# Arak-DAC.net
KiCad netlist of a schematic drawn in Altium Designer
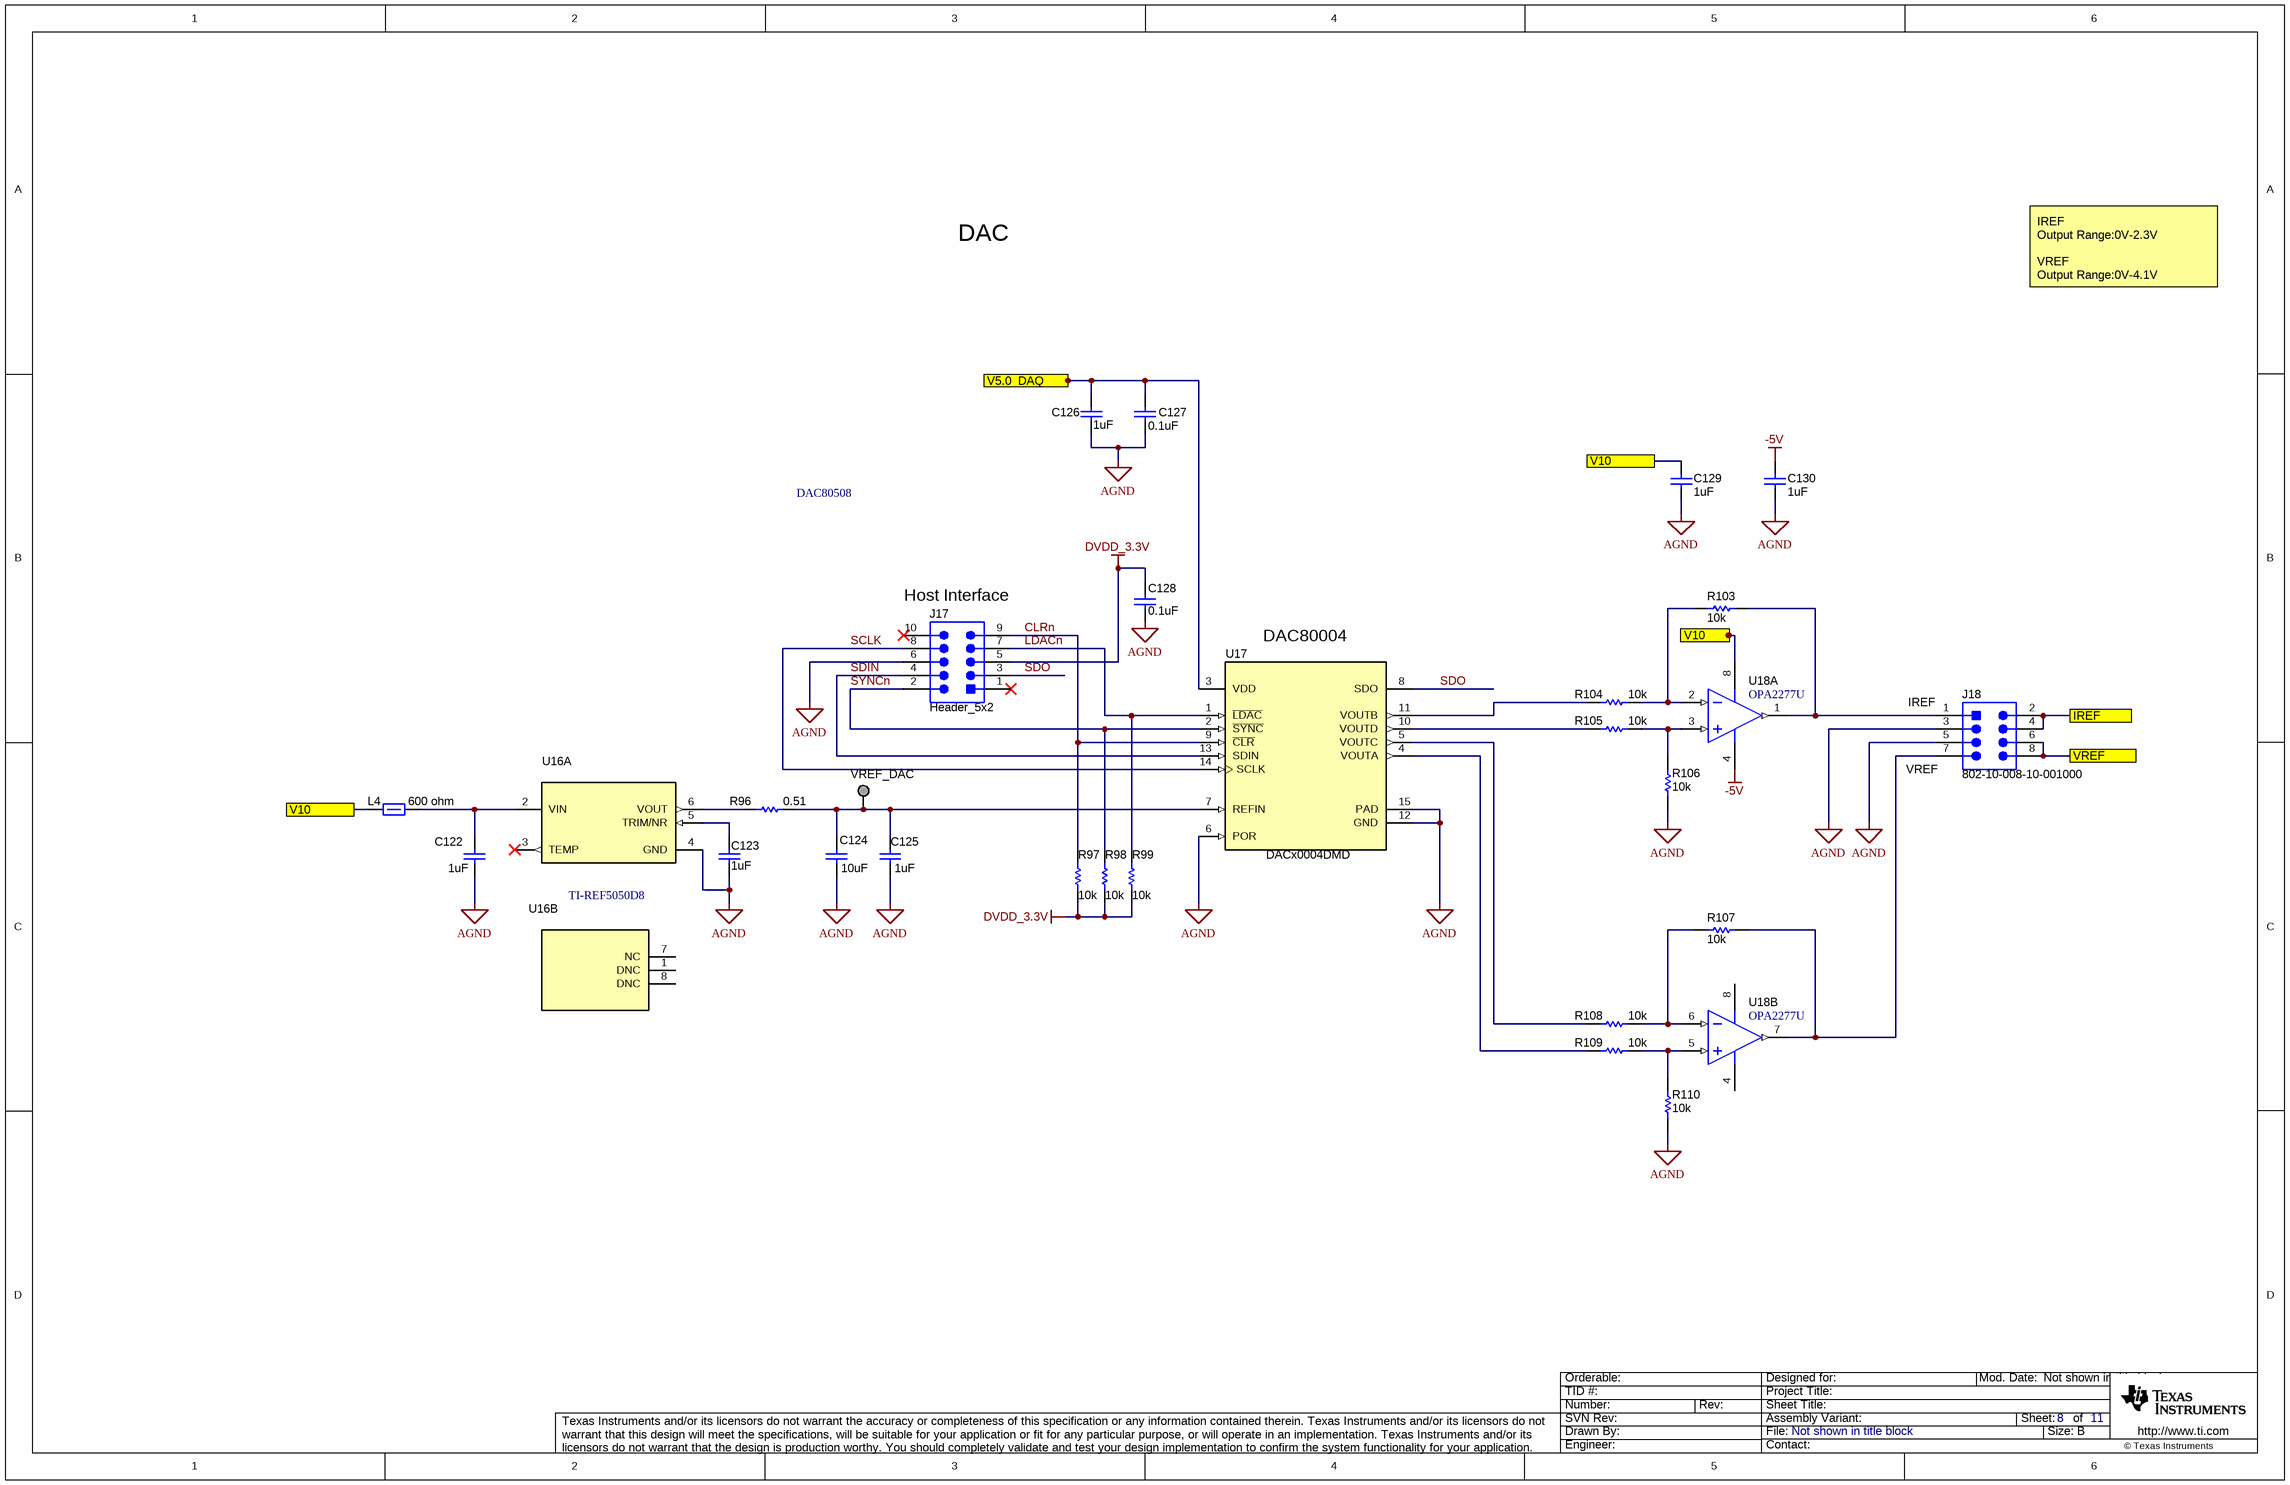
[diagram p0: Arak-DAC.SchDoc]

(export (version "E")
  (design (tool "Eeschema 10.0.6"))
  (components
    (comp (ref "C122")
      (value "Capacitor")
      (footprint "1206")
      (description "CAP, CERM, 1 uF, 25 V, +/- 10%, X7R, 1206")
      (fields
        (field (name "PARTNUMBER") "12063C105KAT2A")
        (field (name "VALUEDISPLAYED") "1uF")
        (field (name "MANUFACTURER") "AVX")
        (field (name "PUBLISHER") "Texas Instruments")
      )
      (libsource (lib "Altium Vault - TI") (part "CMP-0008509-2"))
    )
    (comp (ref "C123")
      (value "Capacitor")
      (footprint "1206")
      (description "CAP, CERM, 1 uF, 25 V, +/- 10%, X7R, 1206")
      (fields
        (field (name "PARTNUMBER") "12063C105KAT2A")
        (field (name "VALUEDISPLAYED") "1uF")
        (field (name "MANUFACTURER") "AVX")
        (field (name "PUBLISHER") "Texas Instruments")
      )
      (libsource (lib "Altium Vault - TI") (part "CMP-0008509-2"))
    )
    (comp (ref "C124")
      (value "Capacitor")
      (footprint "0805_HV")
      (description "CAP, CERM, 10 uF, 35 V, +/- 10%, X6S, 0805")
      (fields
        (field (name "PARTNUMBER") "GRM21BC8YA106KE11L")
        (field (name "VALUEDISPLAYED") "10uF")
        (field (name "MANUFACTURER") "MuRata")
        (field (name "PUBLISHER") "Texas Instruments")
      )
      (libsource (lib "Altium Vault - TI") (part "CMP-0008273-1"))
    )
    (comp (ref "C125")
      (value "Capacitor")
      (footprint "1206")
      (description "CAP, CERM, 1 uF, 25 V, +/- 10%, X7R, 1206")
      (fields
        (field (name "PARTNUMBER") "12063C105KAT2A")
        (field (name "VALUEDISPLAYED") "1uF")
        (field (name "MANUFACTURER") "AVX")
        (field (name "PUBLISHER") "Texas Instruments")
      )
      (libsource (lib "Altium Vault - TI") (part "CMP-0008509-2"))
    )
    (comp (ref "C126")
      (value "Capacitor")
      (footprint "1206")
      (description "CAP, CERM, 1 uF, 25 V, +/- 10%, X7R, 1206")
      (fields
        (field (name "PARTNUMBER") "12063C105KAT2A")
        (field (name "VALUEDISPLAYED") "1uF")
        (field (name "MANUFACTURER") "AVX")
        (field (name "PUBLISHER") "Texas Instruments")
      )
      (libsource (lib "Altium Vault - TI") (part "CMP-0008509-2"))
    )
    (comp (ref "C127")
      (value "Capacitor")
      (footprint "0603")
      (description "CAP, CERM, 0.1 uF, 16 V, +/- 5%, X7R, 0603")
      (fields
        (field (name "PARTNUMBER") "C0603C104J4RACTU")
        (field (name "VALUEDISPLAYED") "0.1uF")
        (field (name "MANUFACTURER") "Kemet")
        (field (name "PUBLISHER") "Texas Instruments")
      )
      (libsource (lib "Altium Vault - TI") (part "CMP-0006857-4"))
    )
    (comp (ref "C128")
      (value "Capacitor")
      (footprint "0603")
      (description "CAP, CERM, 0.1 uF, 16 V, +/- 5%, X7R, 0603")
      (fields
        (field (name "PARTNUMBER") "C0603C104J4RACTU")
        (field (name "VALUEDISPLAYED") "0.1uF")
        (field (name "MANUFACTURER") "Kemet")
        (field (name "PUBLISHER") "Texas Instruments")
      )
      (libsource (lib "Altium Vault - TI") (part "CMP-0006857-4"))
    )
    (comp (ref "C129")
      (value "Capacitor")
      (footprint "0603")
      (description "CAP, CERM, 1 uF, 35 V, +/- 10%, X7R, AEC-Q200 Grade 1, 0603")
      (fields
        (field (name "PARTNUMBER") "CGA3E1X7R1V105K080AC")
        (field (name "VALUEDISPLAYED") "1uF")
        (field (name "MANUFACTURER") "TDK")
        (field (name "PUBLISHER") "Texas Instruments")
      )
      (libsource (lib "Altium Vault - TI") (part "CMP-0007067-4"))
    )
    (comp (ref "C130")
      (value "Capacitor")
      (footprint "0603")
      (description "CAP, CERM, 1 uF, 35 V, +/- 10%, X7R, AEC-Q200 Grade 1, 0603")
      (fields
        (field (name "PARTNUMBER") "CGA3E1X7R1V105K080AC")
        (field (name "VALUEDISPLAYED") "1uF")
        (field (name "MANUFACTURER") "TDK")
        (field (name "PUBLISHER") "Texas Instruments")
      )
      (libsource (lib "Altium Vault - TI") (part "CMP-0007067-4"))
    )
    (comp (ref "J17")
      (value "Header_5x2")
      (footprint "Assman_AWHW-10G-0x02-T")
      (description "Header(Shrouded), 2.54mm, 5x2, Gold, TH")
      (fields
        (field (name "PARTNUMBER") "AWHW-10G-0202-T")
        (field (name "MANUFACTURER") "Assman WSW")
        (field (name "PUBLISHER") "Texas Instruments")
      )
      (libsource (lib "Altium Vault - TI") (part "CMP-0075161-1"))
    )
    (comp (ref "J18")
      (value "802-10-008-10-001000")
      (footprint "Mill-Max_802-10-008-10-001000")
      (description "Header, 2.54 mm, 4x2, Gold, TH")
      (fields (field (name "MANUFACTURER") "Mill-Max") (field (name "PUBLISHER") "Texas Instruments"))
      (libsource (lib "Altium Vault - TI") (part "CMP-0055096-1"))
    )
    (comp (ref "L4")
      (value "600 ohm")
      (footprint "0603")
      (description "Ferrite Bead, 600 ohm @ 100 MHz, 1 A, 0603")
      (fields
        (field (name "PARTNUMBER") "742792651")
        (field (name "MANUFACTURER") "Wurth Elektronik")
        (field (name "PUBLISHER") "Texas Instruments")
      )
      (libsource (lib "Altium Vault - TI") (part "Ferrite_Bead"))
    )
    (comp (ref "R96")
      (value "Resistor")
      (footprint "0603")
      (description "RES, 0.51, 1%, 0.1 W, AEC-Q200 Grade 1, 0603")
      (fields
        (field (name "PARTNUMBER") "ERJ-3RQFR51V")
        (field (name "VALUEDISPLAYED") "0.51")
        (field (name "MANUFACTURER") "Panasonic")
        (field (name "PUBLISHER") "Texas Instruments")
      )
      (libsource (lib "Altium Vault - TI") (part "CMP-0022717-2"))
    )
    (comp (ref "R97")
      (value "Resistor")
      (footprint "0603")
      (description "RES, 10 k, 5%, 0.1 W, AEC-Q200 Grade 0, 0603")
      (fields
        (field (name "PARTNUMBER") "CRCW060310K0JNEA")
        (field (name "VALUEDISPLAYED") "10k")
        (field (name "MANUFACTURER") "Vishay-Dale")
      )
      (libsource (lib "Altium Vault - TI") (part "CMP-0025701-4"))
    )
    (comp (ref "R98")
      (value "Resistor")
      (footprint "0603")
      (description "RES, 10 k, 5%, 0.1 W, AEC-Q200 Grade 0, 0603")
      (fields
        (field (name "PARTNUMBER") "CRCW060310K0JNEA")
        (field (name "VALUEDISPLAYED") "10k")
        (field (name "MANUFACTURER") "Vishay-Dale")
      )
      (libsource (lib "Altium Vault - TI") (part "CMP-0025701-4"))
    )
    (comp (ref "R99")
      (value "Resistor")
      (footprint "0603")
      (description "RES, 10 k, 5%, 0.1 W, AEC-Q200 Grade 0, 0603")
      (fields
        (field (name "PARTNUMBER") "CRCW060310K0JNEA")
        (field (name "VALUEDISPLAYED") "10k")
        (field (name "MANUFACTURER") "Vishay-Dale")
      )
      (libsource (lib "Altium Vault - TI") (part "CMP-0025701-4"))
    )
    (comp (ref "R103")
      (value "Resistor")
      (footprint "0603")
      (description "RES, 10 k, 5%, 0.1 W, AEC-Q200 Grade 0, 0603")
      (fields
        (field (name "PARTNUMBER") "CRCW060310K0JNEA")
        (field (name "VALUEDISPLAYED") "10k")
        (field (name "MANUFACTURER") "Vishay-Dale")
      )
      (libsource (lib "Altium Vault - TI") (part "CMP-0025701-4"))
    )
    (comp (ref "R104")
      (value "Resistor")
      (footprint "0603")
      (description "RES, 10 k, 5%, 0.1 W, AEC-Q200 Grade 0, 0603")
      (fields
        (field (name "PARTNUMBER") "CRCW060310K0JNEA")
        (field (name "VALUEDISPLAYED") "10k")
        (field (name "MANUFACTURER") "Vishay-Dale")
      )
      (libsource (lib "Altium Vault - TI") (part "CMP-0025701-4"))
    )
    (comp (ref "R105")
      (value "Resistor")
      (footprint "0603")
      (description "RES, 10 k, 5%, 0.1 W, AEC-Q200 Grade 0, 0603")
      (fields
        (field (name "PARTNUMBER") "CRCW060310K0JNEA")
        (field (name "VALUEDISPLAYED") "10k")
        (field (name "MANUFACTURER") "Vishay-Dale")
      )
      (libsource (lib "Altium Vault - TI") (part "CMP-0025701-4"))
    )
    (comp (ref "R106")
      (value "Resistor")
      (footprint "0603")
      (description "RES, 10 k, 5%, 0.1 W, AEC-Q200 Grade 0, 0603")
      (fields
        (field (name "PARTNUMBER") "CRCW060310K0JNEA")
        (field (name "VALUEDISPLAYED") "10k")
        (field (name "MANUFACTURER") "Vishay-Dale")
      )
      (libsource (lib "Altium Vault - TI") (part "CMP-0025701-4"))
    )
    (comp (ref "R107")
      (value "Resistor")
      (footprint "0603")
      (description "RES, 10 k, 5%, 0.1 W, AEC-Q200 Grade 0, 0603")
      (fields
        (field (name "PARTNUMBER") "CRCW060310K0JNEA")
        (field (name "VALUEDISPLAYED") "10k")
        (field (name "MANUFACTURER") "Vishay-Dale")
      )
      (libsource (lib "Altium Vault - TI") (part "CMP-0025701-4"))
    )
    (comp (ref "R108")
      (value "Resistor")
      (footprint "0603")
      (description "RES, 10 k, 5%, 0.1 W, AEC-Q200 Grade 0, 0603")
      (fields
        (field (name "PARTNUMBER") "CRCW060310K0JNEA")
        (field (name "VALUEDISPLAYED") "10k")
        (field (name "MANUFACTURER") "Vishay-Dale")
      )
      (libsource (lib "Altium Vault - TI") (part "CMP-0025701-4"))
    )
    (comp (ref "R109")
      (value "Resistor")
      (footprint "0603")
      (description "RES, 10 k, 5%, 0.1 W, AEC-Q200 Grade 0, 0603")
      (fields
        (field (name "PARTNUMBER") "CRCW060310K0JNEA")
        (field (name "VALUEDISPLAYED") "10k")
        (field (name "MANUFACTURER") "Vishay-Dale")
      )
      (libsource (lib "Altium Vault - TI") (part "CMP-0025701-4"))
    )
    (comp (ref "R110")
      (value "Resistor")
      (footprint "0603")
      (description "RES, 10 k, 5%, 0.1 W, AEC-Q200 Grade 0, 0603")
      (fields
        (field (name "PARTNUMBER") "CRCW060310K0JNEA")
        (field (name "VALUEDISPLAYED") "10k")
        (field (name "MANUFACTURER") "Vishay-Dale")
      )
      (libsource (lib "Altium Vault - TI") (part "CMP-0025701-4"))
    )
    (comp (ref "U16")
      (value "TI-REF5050D8")
      (footprint "D0008A_N")
      (fields (field (name "PARTNUMBER") "REF5050AID") (field (name "MANUFACTURER") "Texas Instruments"))
      (libsource (lib "Altium Vault - TI") (part "CMP-0032617-1"))
    )
    (comp (ref "U17")
      (value "DACx0004DMD")
      (footprint "DMD0014A")
      (description "QUAD 16-BIT, 1LSB INL, BUFFERED, VOLTAGE-OUTPUT DIGITAL-to-ANALOG CONVERTERS, DMD0014A (VSON-14)")
      (fields
        (field (name "PARTNUMBER") "DAC80004IDMD")
        (field (name "MANUFACTURER") "Texas Instruments")
        (field (name "PUBLISHER") "Texas Instruments")
      )
      (libsource (lib "Altium Vault - TI") (part "DACx0004DMD"))
    )
    (comp (ref "U18")
      (value "OPA2277U")
      (footprint "D0008A_N")
      (fields (field (name "MANUFACTURER") "Texas Instruments"))
      (libsource (lib "Altium Vault - TI") (part "CMP-0040655-1"))
    )
    (comp (ref "VREF_DAC")
      (value "Pogo Pad")
      (footprint "PogoPad")
      (description "Pad for Pogo Pin Connector")
      (fields (field (name "SYMBOLCREATOR") "codlsc") (field (name "PUBLISHER") "Texas Instruments"))
      (libsource (lib "MiscParts") (part "PogoPad"))
    )
  )
  (nets
    (net (code "1") (name "-5V") (class "Default")
      (node (ref "C130") (pin "1") (pinfunction "1_1") (pintype "passive"))
      (node (ref "U18") (pin "4") (pinfunction "V-_4") (pintype "power_in"))
    )
    (net (code "2") (name "/CLRn") (class "Default")
      (node (ref "J17") (pin "9") (pinfunction "9_9") (pintype "passive"))
      (node (ref "R97") (pin "2") (pinfunction "2_2") (pintype "passive"))
      (node (ref "U17") (pin "9") (pinfunction "CLR_9") (pintype "input"))
    )
    (net (code "3") (name "/IREF") (class "Default")
      (node (ref "J18") (pin "2") (pinfunction "2_2") (pintype "passive"))
      (node (ref "J18") (pin "4") (pinfunction "4_4") (pintype "passive"))
    )
    (net (code "4") (name "/LDACn") (class "Default")
      (node (ref "J17") (pin "7") (pinfunction "7_7") (pintype "passive"))
      (node (ref "R99") (pin "2") (pinfunction "2_2") (pintype "passive"))
      (node (ref "U17") (pin "1") (pinfunction "LDAC_1") (pintype "input"))
    )
    (net (code "5") (name "/SCLK") (class "Default")
      (node (ref "J17") (pin "8") (pinfunction "8_8") (pintype "passive"))
      (node (ref "U17") (pin "14") (pinfunction "SCLK_14") (pintype "input"))
    )
    (net (code "6") (name "/SDIN") (class "Default")
      (node (ref "J17") (pin "4") (pinfunction "4_4") (pintype "passive"))
      (node (ref "U17") (pin "13") (pinfunction "SDIN_13") (pintype "input"))
    )
    (net (code "7") (name "/SDO") (class "Default")
      (node (ref "J17") (pin "3") (pinfunction "3_3") (pintype "passive"))
      (node (ref "U17") (pin "8") (pinfunction "SDO_8") (pintype "tri_state"))
    )
    (net (code "8") (name "/SYNCn") (class "Default")
      (node (ref "J17") (pin "2") (pinfunction "2_2") (pintype "passive"))
      (node (ref "R98") (pin "2") (pinfunction "2_2") (pintype "passive"))
      (node (ref "U17") (pin "2") (pinfunction "SYNC_2") (pintype "input"))
    )
    (net (code "9") (name "/V5.0_DAQ") (class "Default")
      (node (ref "C126") (pin "1") (pinfunction "1_1") (pintype "passive"))
      (node (ref "C127") (pin "1") (pinfunction "1_1") (pintype "passive"))
      (node (ref "U17") (pin "3") (pinfunction "VDD_3") (pintype "power_in"))
    )
    (net (code "10") (name "/V10") (class "Default")
      (node (ref "C129") (pin "1") (pinfunction "1_1") (pintype "passive"))
      (node (ref "L4") (pin "1") (pinfunction "1_1") (pintype "passive"))
      (node (ref "U18") (pin "8") (pinfunction "V+_8") (pintype "power_in"))
    )
    (net (code "11") (name "/VREF") (class "Default")
      (node (ref "J18") (pin "6") (pinfunction "6_6") (pintype "passive"))
      (node (ref "J18") (pin "8") (pinfunction "8_8") (pintype "passive"))
    )
    (net (code "12") (name "AGND") (class "Default")
      (node (ref "C122") (pin "2") (pinfunction "2_2") (pintype "passive"))
      (node (ref "C123") (pin "2") (pinfunction "2_2") (pintype "passive"))
      (node (ref "C124") (pin "2") (pinfunction "2_2") (pintype "passive"))
      (node (ref "C125") (pin "2") (pinfunction "2_2") (pintype "passive"))
      (node (ref "C126") (pin "2") (pinfunction "2_2") (pintype "passive"))
      (node (ref "C127") (pin "2") (pinfunction "2_2") (pintype "passive"))
      (node (ref "C128") (pin "2") (pinfunction "2_2") (pintype "passive"))
      (node (ref "C129") (pin "2") (pinfunction "2_2") (pintype "passive"))
      (node (ref "C130") (pin "2") (pinfunction "2_2") (pintype "passive"))
      (node (ref "J17") (pin "6") (pinfunction "6_6") (pintype "passive"))
      (node (ref "J18") (pin "3") (pinfunction "3_3") (pintype "passive"))
      (node (ref "J18") (pin "5") (pinfunction "5_5") (pintype "passive"))
      (node (ref "R106") (pin "1") (pinfunction "1_1") (pintype "passive"))
      (node (ref "R110") (pin "1") (pinfunction "1_1") (pintype "passive"))
      (node (ref "U16") (pin "4") (pinfunction "GND_4") (pintype "power_in"))
      (node (ref "U17") (pin "12") (pinfunction "GND_12") (pintype "power_in"))
      (node (ref "U17") (pin "15") (pinfunction "PAD_15") (pintype "passive"))
      (node (ref "U17") (pin "6") (pinfunction "POR_6") (pintype "input"))
    )
    (net (code "13") (name "DVDD_3.3V") (class "Default")
      (node (ref "C128") (pin "1") (pinfunction "1_1") (pintype "passive"))
      (node (ref "J17") (pin "5") (pinfunction "5_5") (pintype "passive"))
      (node (ref "R97") (pin "1") (pinfunction "1_1") (pintype "passive"))
      (node (ref "R98") (pin "1") (pinfunction "1_1") (pintype "passive"))
      (node (ref "R99") (pin "1") (pinfunction "1_1") (pintype "passive"))
    )
    (net (code "14") (name "Net-(U16A-TRIM{slash}NR)") (class "Default")
      (node (ref "C123") (pin "1") (pinfunction "1_1") (pintype "passive"))
      (node (ref "U16") (pin "5") (pinfunction "TRIM/NR_5") (pintype "input"))
    )
    (net (code "15") (name "Net-(U16A-VIN)") (class "Default")
      (node (ref "C122") (pin "1") (pinfunction "1_1") (pintype "passive"))
      (node (ref "L4") (pin "2") (pinfunction "2_2") (pintype "passive"))
      (node (ref "U16") (pin "2") (pinfunction "VIN_2") (pintype "power_in"))
    )
    (net (code "16") (name "Net-(U16A-VOUT)") (class "Default")
      (node (ref "R96") (pin "1") (pinfunction "1_1") (pintype "passive"))
      (node (ref "U16") (pin "6") (pinfunction "VOUT_6") (pintype "output"))
    )
    (net (code "17") (name "Net-(U17-REFIN)") (class "Default")
      (node (ref "C124") (pin "1") (pinfunction "1_1") (pintype "passive"))
      (node (ref "C125") (pin "1") (pinfunction "1_1") (pintype "passive"))
      (node (ref "R96") (pin "2") (pinfunction "2_2") (pintype "passive"))
      (node (ref "U17") (pin "7") (pinfunction "REFIN_7") (pintype "input"))
      (node (ref "VREF_DAC") (pin "1") (pintype "passive"))
    )
    (net (code "18") (name "Net-(U17-VOUTA)") (class "Default")
      (node (ref "R109") (pin "2") (pinfunction "2_2") (pintype "passive"))
      (node (ref "U17") (pin "4") (pinfunction "VOUTA_4") (pintype "output"))
    )
    (net (code "19") (name "Net-(U17-VOUTB)") (class "Default")
      (node (ref "R104") (pin "2") (pinfunction "2_2") (pintype "passive"))
      (node (ref "U17") (pin "11") (pinfunction "VOUTB_11") (pintype "output"))
    )
    (net (code "20") (name "Net-(U17-VOUTC)") (class "Default")
      (node (ref "R108") (pin "2") (pinfunction "2_2") (pintype "passive"))
      (node (ref "U17") (pin "5") (pinfunction "VOUTC_5") (pintype "output"))
    )
    (net (code "21") (name "Net-(U17-VOUTD)") (class "Default")
      (node (ref "R105") (pin "2") (pinfunction "2_2") (pintype "passive"))
      (node (ref "U17") (pin "10") (pinfunction "VOUTD_10") (pintype "output"))
    )
    (net (code "22") (name "Net-(U18A-IN_A+)") (class "Default")
      (node (ref "R105") (pin "1") (pinfunction "1_1") (pintype "passive"))
      (node (ref "R106") (pin "2") (pinfunction "2_2") (pintype "passive"))
      (node (ref "U18") (pin "3") (pinfunction "IN_A+_3") (pintype "input"))
    )
    (net (code "23") (name "Net-(U18A-IN_A-)") (class "Default")
      (node (ref "R103") (pin "2") (pinfunction "2_2") (pintype "passive"))
      (node (ref "R104") (pin "1") (pinfunction "1_1") (pintype "passive"))
      (node (ref "U18") (pin "2") (pinfunction "IN_A-_2") (pintype "input"))
    )
    (net (code "24") (name "Net-(U18A-OUT_A)") (class "Default")
      (node (ref "J18") (pin "1") (pinfunction "1_1") (pintype "passive"))
      (node (ref "R103") (pin "1") (pinfunction "1_1") (pintype "passive"))
      (node (ref "U18") (pin "1") (pinfunction "OUT_A_1") (pintype "output"))
    )
    (net (code "25") (name "Net-(U18B-IN_B+)") (class "Default")
      (node (ref "R109") (pin "1") (pinfunction "1_1") (pintype "passive"))
      (node (ref "R110") (pin "2") (pinfunction "2_2") (pintype "passive"))
      (node (ref "U18") (pin "5") (pinfunction "IN_B+_5") (pintype "input"))
    )
    (net (code "26") (name "Net-(U18B-IN_B-)") (class "Default")
      (node (ref "R107") (pin "2") (pinfunction "2_2") (pintype "passive"))
      (node (ref "R108") (pin "1") (pinfunction "1_1") (pintype "passive"))
      (node (ref "U18") (pin "6") (pinfunction "IN_B-_6") (pintype "input"))
    )
    (net (code "27") (name "Net-(U18B-OUT_B)") (class "Default")
      (node (ref "J18") (pin "7") (pinfunction "7_7") (pintype "passive"))
      (node (ref "R107") (pin "1") (pinfunction "1_1") (pintype "passive"))
      (node (ref "U18") (pin "7") (pinfunction "OUT_B_7") (pintype "output"))
    )
    (net (code "28") (name "unconnected-(J17-Pad1)") (class "Default")
      (node (ref "J17") (pin "1") (pinfunction "1_1") (pintype "passive+no_connect"))
    )
    (net (code "29") (name "unconnected-(J17-Pad10)") (class "Default")
      (node (ref "J17") (pin "10") (pinfunction "10_10") (pintype "passive+no_connect"))
    )
    (net (code "30") (name "unconnected-(U16A-TEMP-Pad3)") (class "Default")
      (node (ref "U16") (pin "3") (pinfunction "TEMP_3") (pintype "output+no_connect"))
    )
    (net (code "31") (name "unconnected-(U16B-DNC-Pad1)") (class "Default")
      (node (ref "U16") (pin "1") (pinfunction "DNC_1") (pintype "passive"))
    )
    (net (code "32") (name "unconnected-(U16B-DNC-Pad8)") (class "Default")
      (node (ref "U16") (pin "8") (pinfunction "DNC_8") (pintype "passive"))
    )
    (net (code "33") (name "unconnected-(U16B-NC-Pad7)") (class "Default")
      (node (ref "U16") (pin "7") (pinfunction "NC_7") (pintype "passive"))
    )
    (net (code "34") (name "unconnected-(U18B-V+-Pad8)") (class "Default")
      (node (ref "U18") (pin "8") (pinfunction "V+_8") (pintype "power_in"))
    )
    (net (code "35") (name "unconnected-(U18B-V--Pad4)") (class "Default")
      (node (ref "U18") (pin "4") (pinfunction "V-_4") (pintype "power_in"))
    )
  )
)
